# side_small.net
KiCad netlist of a schematic drawn in EAGLE
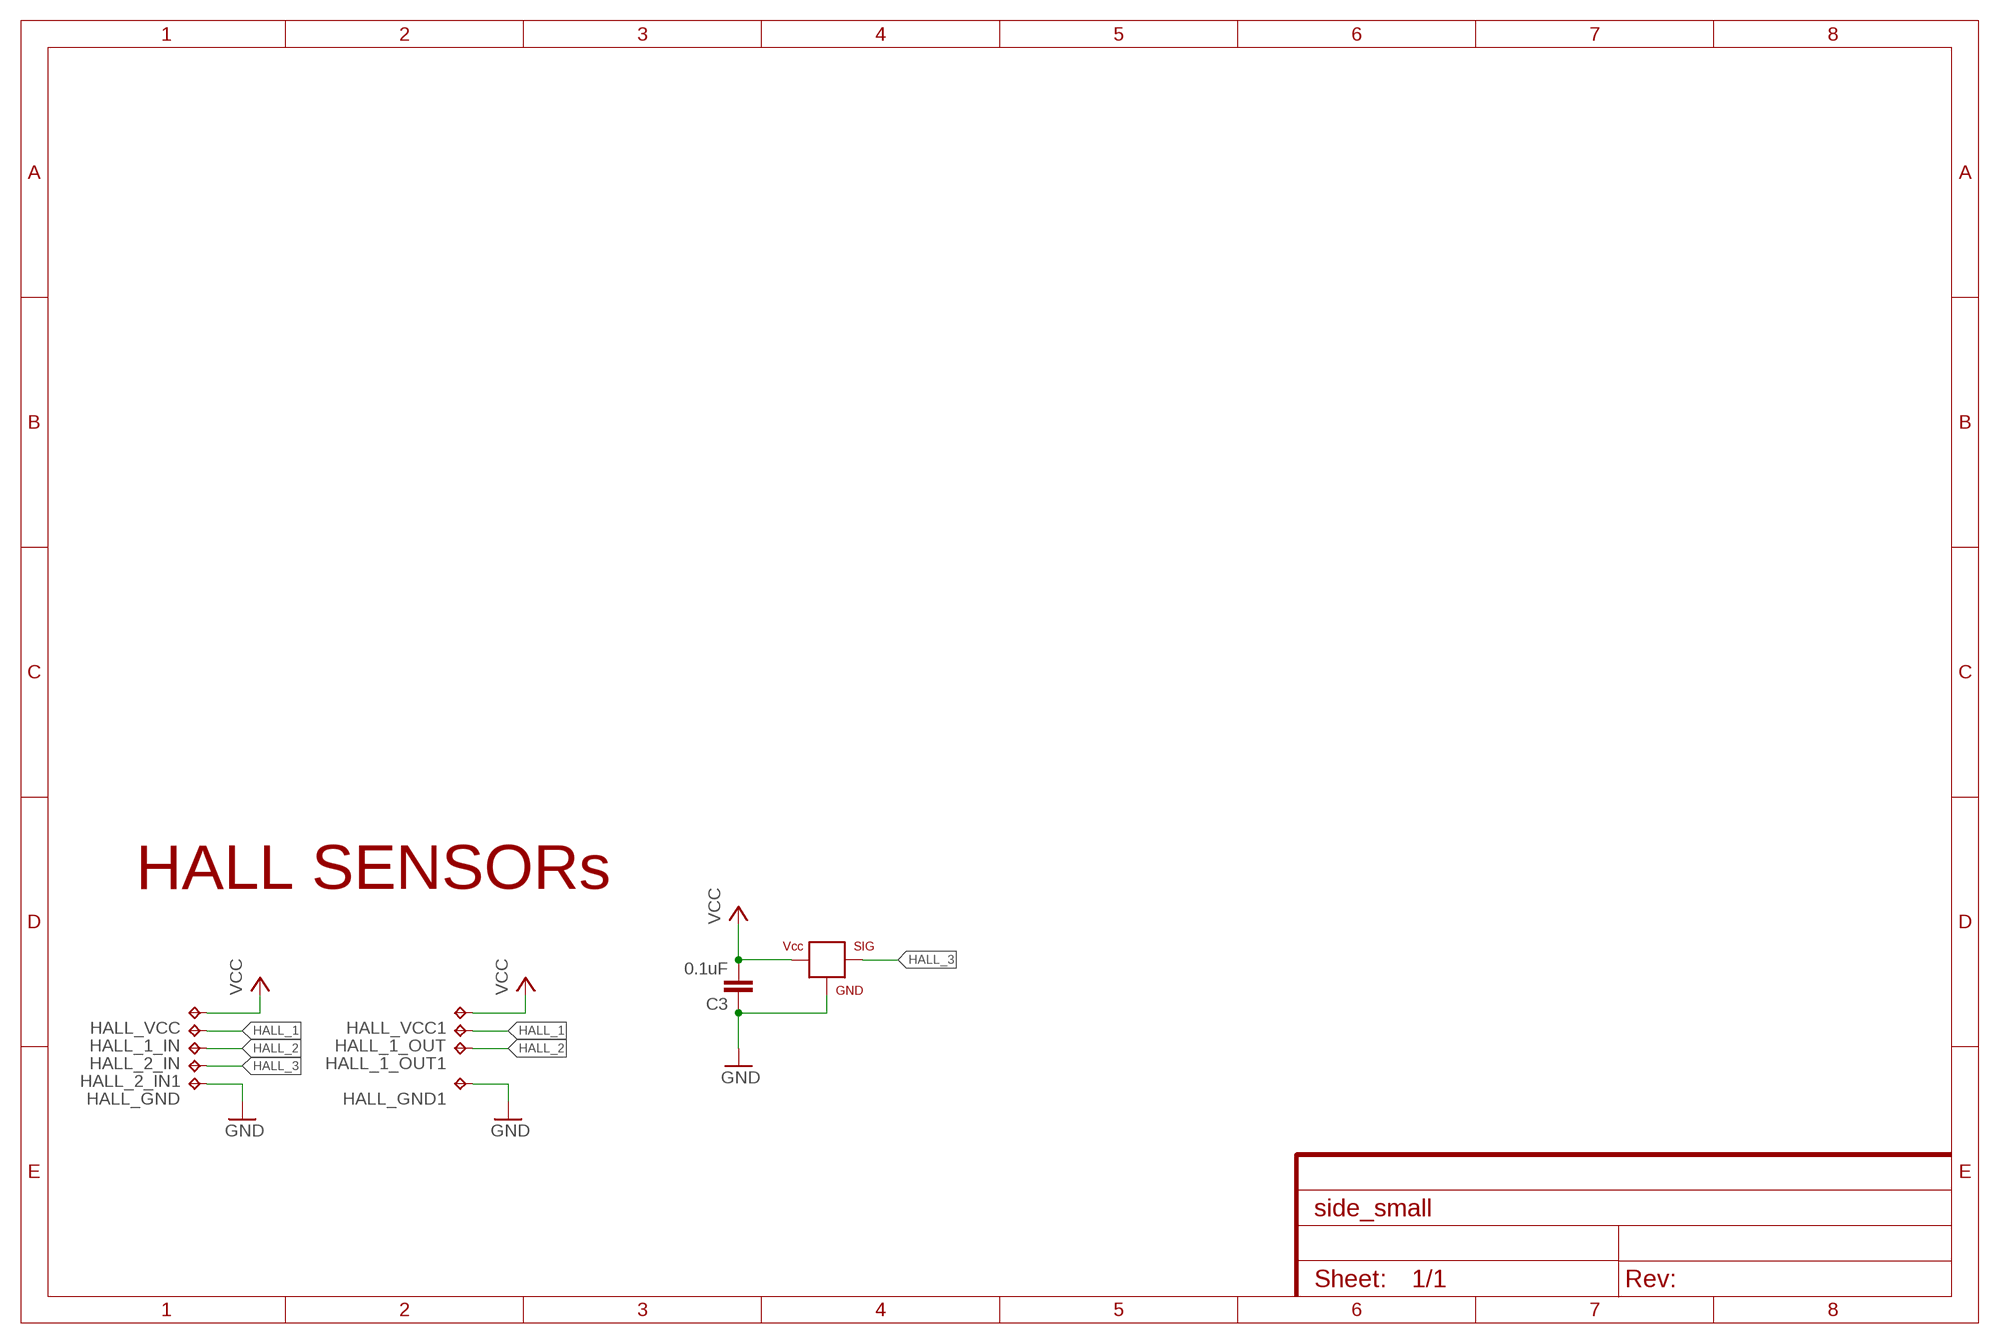
[diagram p0: schematic, sheet 1]

(export (version "E")
  (design (tool "Eeschema 10.0.6"))
  (components
    (comp (ref "C3")
      (value "0.1uF")
      (footprint "eagle-import:0603-CAP")
      (libsource (lib "eagle-import") (part "CAP0603-CAP"))
    )
    (comp (ref "HALL")
      (value "HALLEFFECT-A1326")
      (footprint "eagle-import:SOT23-3")
      (libsource (lib "eagle-import") (part "HALLEFFECT-A1326"))
    )
    (comp (ref "HALL_1_IN")
      (value "TPTP20SQ")
      (footprint "eagle-import:TP20SQ")
      (libsource (lib "eagle-import") (part "TPTP20SQ"))
    )
    (comp (ref "HALL_1_OUT")
      (value "TPTP20SQ")
      (footprint "eagle-import:TP20SQ")
      (libsource (lib "eagle-import") (part "TPTP20SQ"))
    )
    (comp (ref "HALL_1_OUT1")
      (value "TPTP20SQ")
      (footprint "eagle-import:TP20SQ")
      (libsource (lib "eagle-import") (part "TPTP20SQ"))
    )
    (comp (ref "HALL_2_IN")
      (value "TPTP20SQ")
      (footprint "eagle-import:TP20SQ")
      (libsource (lib "eagle-import") (part "TPTP20SQ"))
    )
    (comp (ref "HALL_2_IN1")
      (value "TPTP20SQ")
      (footprint "eagle-import:TP20SQ")
      (libsource (lib "eagle-import") (part "TPTP20SQ"))
    )
    (comp (ref "HALL_GND")
      (value "TPTP20SQ")
      (footprint "eagle-import:TP20SQ")
      (libsource (lib "eagle-import") (part "TPTP20SQ"))
    )
    (comp (ref "HALL_GND1")
      (value "TPTP20SQ")
      (footprint "eagle-import:TP20SQ")
      (libsource (lib "eagle-import") (part "TPTP20SQ"))
    )
    (comp (ref "HALL_VCC")
      (value "TPTP20SQ")
      (footprint "eagle-import:TP20SQ")
      (libsource (lib "eagle-import") (part "TPTP20SQ"))
    )
    (comp (ref "HALL_VCC1")
      (value "TPTP20SQ")
      (footprint "eagle-import:TP20SQ")
      (libsource (lib "eagle-import") (part "TPTP20SQ"))
    )
  )
  (nets
    (net (code "1") (name "GND") (class "Default")
      (node (ref "C3") (pin "1") (pinfunction "1_1") (pintype "passive"))
      (node (ref "HALL") (pin "3") (pinfunction "GND_3") (pintype "bidirectional"))
      (node (ref "HALL_GND") (pin "TP") (pinfunction "TP_TP") (pintype "input"))
      (node (ref "HALL_GND1") (pin "TP") (pinfunction "TP_TP") (pintype "input"))
    )
    (net (code "2") (name "HALL_1") (class "Default")
      (node (ref "HALL_1_IN") (pin "TP") (pinfunction "TP_TP") (pintype "input"))
      (node (ref "HALL_1_OUT") (pin "TP") (pinfunction "TP_TP") (pintype "input"))
    )
    (net (code "3") (name "HALL_2") (class "Default")
      (node (ref "HALL_1_OUT1") (pin "TP") (pinfunction "TP_TP") (pintype "input"))
      (node (ref "HALL_2_IN") (pin "TP") (pinfunction "TP_TP") (pintype "input"))
    )
    (net (code "4") (name "HALL_3") (class "Default")
      (node (ref "HALL") (pin "2") (pinfunction "SIG_2") (pintype "bidirectional"))
      (node (ref "HALL_2_IN1") (pin "TP") (pinfunction "TP_TP") (pintype "input"))
    )
    (net (code "5") (name "VCC") (class "Default")
      (node (ref "C3") (pin "2") (pinfunction "2_2") (pintype "passive"))
      (node (ref "HALL") (pin "1") (pinfunction "VCC_1") (pintype "bidirectional"))
      (node (ref "HALL_VCC") (pin "TP") (pinfunction "TP_TP") (pintype "input"))
      (node (ref "HALL_VCC1") (pin "TP") (pinfunction "TP_TP") (pintype "input"))
    )
  )
)
